# rev02_3.net
KiCad netlist of a schematic drawn in Altium Designer
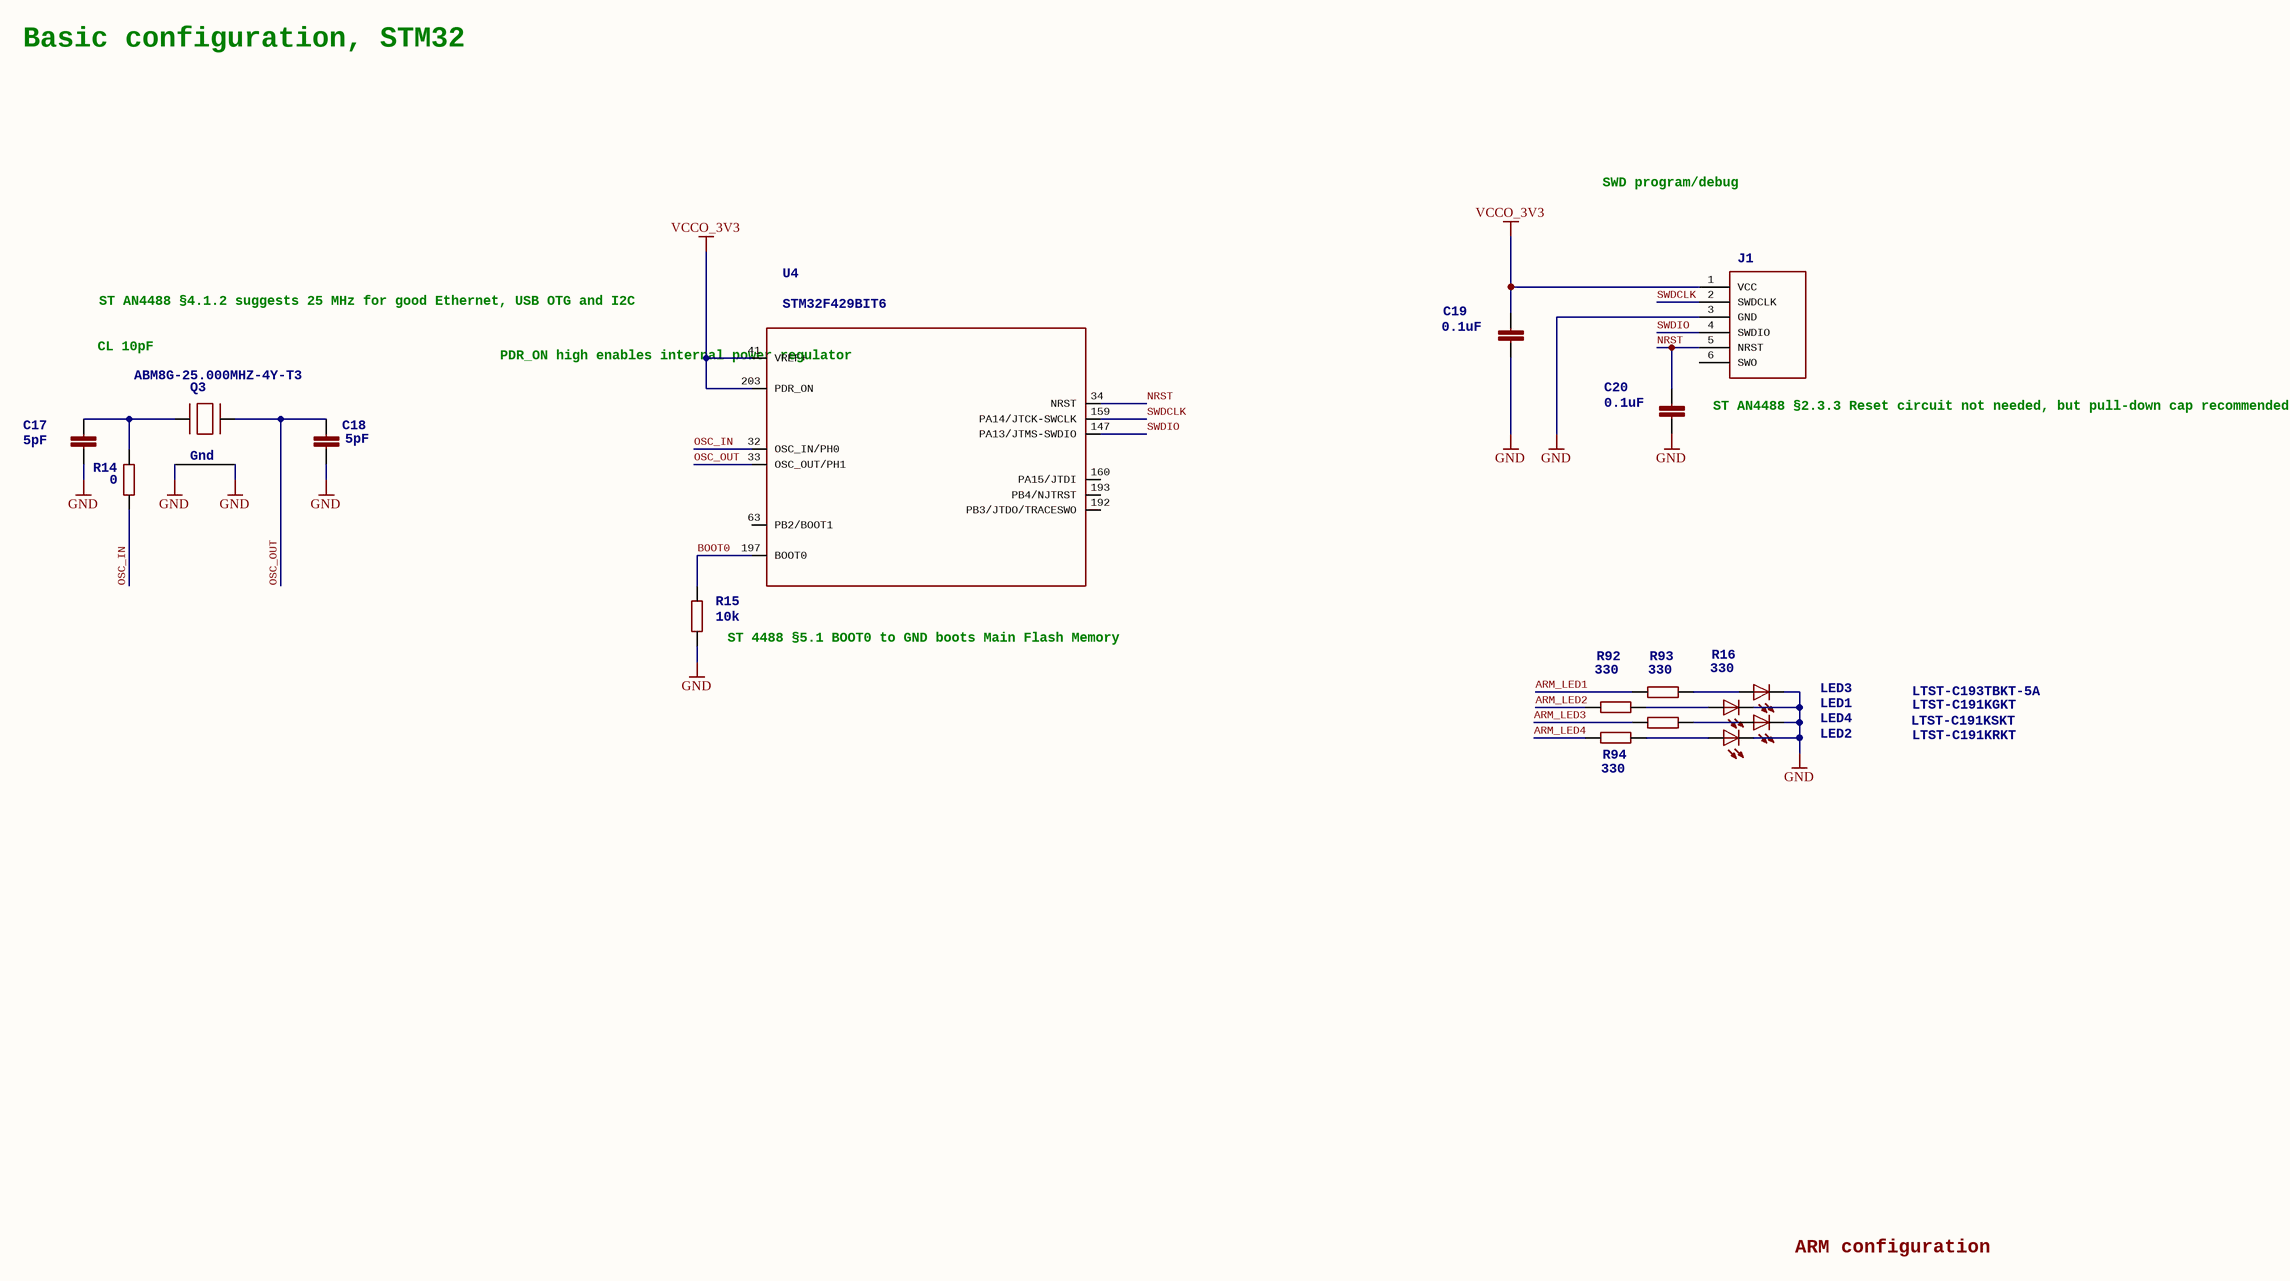
[diagram p0: rev02_3.SchDoc]

(export (version "E")
  (design (tool "Eeschema 10.0.6"))
  (components
    (comp (ref "C17")
      (value "5pF")
      (footprint "C_0402")
      (description "0402 CAPACITOR")
      (libsource (lib "rcl") (part "C-EUC0402"))
    )
    (comp (ref "C18")
      (value "5pF")
      (footprint "C_0402")
      (description "0402 CAPACITOR")
      (libsource (lib "rcl") (part "C-EUC0402"))
    )
    (comp (ref "C19")
      (value "0.1uF")
      (footprint "C_0402")
      (description "0402 CAPACITOR")
      (libsource (lib "resistor") (part "C-EUC0402"))
    )
    (comp (ref "C20")
      (value "0.1uF")
      (footprint "C_0402")
      (description "0402 CAPACITOR")
      (libsource (lib "resistor") (part "C-EUC0402"))
    )
    (comp (ref "J1")
      (value "STM32-SWD")
      (footprint "PLS-6")
      (description "STM32 SWD connector")
      (libsource (lib "rev02_1") (part "STM32-SWD"))
    )
    (comp (ref "LED1")
      (value "LTST-C191KGKT")
      (footprint "VD_0603")
      (description "GREEN LED")
      (libsource (lib "rev02_1") (part "LEDCHIP-LED0603"))
    )
    (comp (ref "LED2")
      (value "LTST-C191KRKT")
      (footprint "VD_0603")
      (description "RED LED")
      (libsource (lib "rev02_1") (part "LEDCHIP-LED0603"))
    )
    (comp (ref "LED3")
      (value "LTST-C193TBKT-5A")
      (footprint "VD_0603")
      (description "BLUE LED")
      (libsource (lib "rev02_1") (part "LEDCHIP-LED0603"))
    )
    (comp (ref "LED4")
      (value "LTST-C191KSKT")
      (footprint "VD_0603")
      (description "YELLOW LED")
      (libsource (lib "rev02_1") (part "LEDCHIP-LED0603"))
    )
    (comp (ref "Q3")
      (value "ABM8G-25.000MHZ-4Y-T3")
      (footprint "CRYSTAL_3.2X2.5")
      (description "Abracon 25MHz 10pF 4-pin 3.2 x 2.5mm crystal")
      (fields (field (name ">NAME") "Q3") (field (name "GND") "Gnd"))
      (libsource (lib "adafruit") (part "XTAL-4-3225"))
    )
    (comp (ref "R14")
      (value "0")
      (footprint "R_0402")
      (description "0402 Resistor 5%")
      (fields (field (name ">NAME") "R14"))
      (libsource (lib "resistor") (part "R-EU_R0402"))
    )
    (comp (ref "R15")
      (value "10k")
      (footprint "R_0402")
      (description "0402 Resistor 5%")
      (fields (field (name "TOLERANCE") "5%") (field (name ">NAME") "R15"))
      (libsource (lib "resistor") (part "R-EU_R0402"))
    )
    (comp (ref "R16")
      (value "330")
      (footprint "R_0402")
      (description "0402 Resistor 5%")
      (libsource (lib "resistor") (part "R-EU_R0402"))
    )
    (comp (ref "R92")
      (value "330")
      (footprint "R_0402")
      (description "0402 Resistor 5%")
      (libsource (lib "resistor") (part "R-EU_R0402"))
    )
    (comp (ref "R93")
      (value "330")
      (footprint "R_0402")
      (description "0402 Resistor 5%")
      (libsource (lib "resistor") (part "R-EU_R0402"))
    )
    (comp (ref "R94")
      (value "330")
      (footprint "R_0402")
      (description "0402 Resistor 5%")
      (libsource (lib "resistor") (part "R-EU_R0402"))
    )
    (comp (ref "U4")
      (value "STM32F429BIT6")
      (description "STM32F429 Cortex-M4 CPU\n180 MHz, 256 KB RAM, 2 MB Flash")
      (fields (field (name ">NAME") "U4") (field (name ">VALUE") "STM32F429BIT6"))
      (libsource (lib "Alpha-IC") (part "STM32F429BIT6"))
    )
  )
  (nets
    (net (code "1") (name "/ARM_LED1") (class "Default")
      (node (ref "R93") (pin "2") (pinfunction "2_2") (pintype "passive"))
    )
    (net (code "2") (name "/ARM_LED2") (class "Default")
      (node (ref "R92") (pin "2") (pinfunction "2_2") (pintype "passive"))
    )
    (net (code "3") (name "/ARM_LED3") (class "Default")
      (node (ref "R16") (pin "2") (pinfunction "2_2") (pintype "passive"))
    )
    (net (code "4") (name "/ARM_LED4") (class "Default")
      (node (ref "R94") (pin "2") (pinfunction "2_2") (pintype "passive"))
    )
    (net (code "5") (name "/BOOT0") (class "Default")
      (node (ref "R15") (pin "2") (pinfunction "2_2") (pintype "passive"))
      (node (ref "U4") (pin "197") (pinfunction "BOOT0_197") (pintype "passive"))
    )
    (net (code "6") (name "/NRST") (class "Default")
      (node (ref "C20") (pin "1") (pinfunction "1_1") (pintype "passive"))
      (node (ref "J1") (pin "5") (pinfunction "NRST_5") (pintype "passive"))
      (node (ref "U4") (pin "34") (pinfunction "NRST_34") (pintype "passive"))
    )
    (net (code "7") (name "/OSC_IN") (class "Default")
      (node (ref "R14") (pin "1") (pinfunction "1_1") (pintype "passive"))
      (node (ref "U4") (pin "32") (pinfunction "OSC_IN/PH0_32") (pintype "passive"))
    )
    (net (code "8") (name "/OSC_OUT") (class "Default")
      (node (ref "C18") (pin "2") (pinfunction "2_2") (pintype "passive"))
      (node (ref "Q3") (pin "3") (pinfunction "X2_3") (pintype "passive"))
      (node (ref "U4") (pin "33") (pinfunction "OSC_OUT/PH1_33") (pintype "passive"))
    )
    (net (code "9") (name "/SWDCLK") (class "Default")
      (node (ref "J1") (pin "2") (pinfunction "SWDCLK_2") (pintype "passive"))
      (node (ref "U4") (pin "159") (pinfunction "PA14/JTCK-SWCLK_159") (pintype "passive"))
    )
    (net (code "10") (name "/SWDIO") (class "Default")
      (node (ref "J1") (pin "4") (pinfunction "SWDIO_4") (pintype "passive"))
      (node (ref "U4") (pin "147") (pinfunction "PA13/JTMS-SWDIO_147") (pintype "passive"))
    )
    (net (code "11") (name "GND") (class "Default")
      (node (ref "C17") (pin "1") (pinfunction "1_1") (pintype "passive"))
      (node (ref "C18") (pin "1") (pinfunction "1_1") (pintype "passive"))
      (node (ref "C19") (pin "2") (pinfunction "2_2") (pintype "passive"))
      (node (ref "C20") (pin "2") (pinfunction "2_2") (pintype "passive"))
      (node (ref "J1") (pin "3") (pinfunction "GND_3") (pintype "power_in"))
      (node (ref "LED1") (pin "2") (pinfunction "C_2") (pintype "passive"))
      (node (ref "LED2") (pin "2") (pinfunction "C_2") (pintype "passive"))
      (node (ref "LED3") (pin "2") (pinfunction "C_2") (pintype "passive"))
      (node (ref "LED4") (pin "2") (pinfunction "C_2") (pintype "passive"))
      (node (ref "Q3") (pin "2") (pinfunction "G2_2") (pintype "power_in"))
      (node (ref "Q3") (pin "4") (pinfunction "G1_4") (pintype "power_in"))
      (node (ref "R15") (pin "1") (pinfunction "1_1") (pintype "passive"))
    )
    (net (code "12") (name "Net-(LED1-A)") (class "Default")
      (node (ref "LED1") (pin "1") (pinfunction "A_1") (pintype "passive"))
      (node (ref "R92") (pin "1") (pinfunction "1_1") (pintype "passive"))
    )
    (net (code "13") (name "Net-(LED2-A)") (class "Default")
      (node (ref "LED2") (pin "1") (pinfunction "A_1") (pintype "passive"))
      (node (ref "R94") (pin "1") (pinfunction "1_1") (pintype "passive"))
    )
    (net (code "14") (name "Net-(LED3-A)") (class "Default")
      (node (ref "LED3") (pin "1") (pinfunction "A_1") (pintype "passive"))
      (node (ref "R93") (pin "1") (pinfunction "1_1") (pintype "passive"))
    )
    (net (code "15") (name "Net-(LED4-A)") (class "Default")
      (node (ref "LED4") (pin "1") (pinfunction "A_1") (pintype "passive"))
      (node (ref "R16") (pin "1") (pinfunction "1_1") (pintype "passive"))
    )
    (net (code "16") (name "Net-(Q3-X1)") (class "Default")
      (node (ref "C17") (pin "2") (pinfunction "2_2") (pintype "passive"))
      (node (ref "Q3") (pin "1") (pinfunction "X1_1") (pintype "passive"))
      (node (ref "R14") (pin "2") (pinfunction "2_2") (pintype "passive"))
    )
    (net (code "17") (name "VCCO_3V3") (class "Default")
      (node (ref "C19") (pin "1") (pinfunction "1_1") (pintype "passive"))
      (node (ref "J1") (pin "1") (pinfunction "VCC_1") (pintype "power_in"))
      (node (ref "U4") (pin "203") (pinfunction "PDR_ON_203") (pintype "passive"))
      (node (ref "U4") (pin "41") (pinfunction "VREF+_41") (pintype "power_in"))
    )
    (net (code "18") (name "unconnected-(J1-SWO-Pad6)") (class "Default")
      (node (ref "J1") (pin "6") (pinfunction "SWO_6") (pintype "passive"))
    )
    (net (code "19") (name "unconnected-(U4B-PA15{slash}JTDI-Pad160)") (class "Default")
      (node (ref "U4") (pin "160") (pinfunction "PA15/JTDI_160") (pintype "passive"))
    )
    (net (code "20") (name "unconnected-(U4B-PB2{slash}BOOT1-Pad63)") (class "Default")
      (node (ref "U4") (pin "63") (pinfunction "PB2/BOOT1_63") (pintype "passive"))
    )
    (net (code "21") (name "unconnected-(U4B-PB3{slash}JTDO{slash}TRACESWO-Pad192)") (class "Default")
      (node (ref "U4") (pin "192") (pinfunction "PB3/JTDO/TRACESWO_192") (pintype "passive"))
    )
    (net (code "22") (name "unconnected-(U4B-PB4{slash}NJTRST-Pad193)") (class "Default")
      (node (ref "U4") (pin "193") (pinfunction "PB4/NJTRST_193") (pintype "passive"))
    )
  )
)
